# AD595_thermocouple_breakout_board-rev2.net
KiCad netlist of a schematic drawn in EAGLE
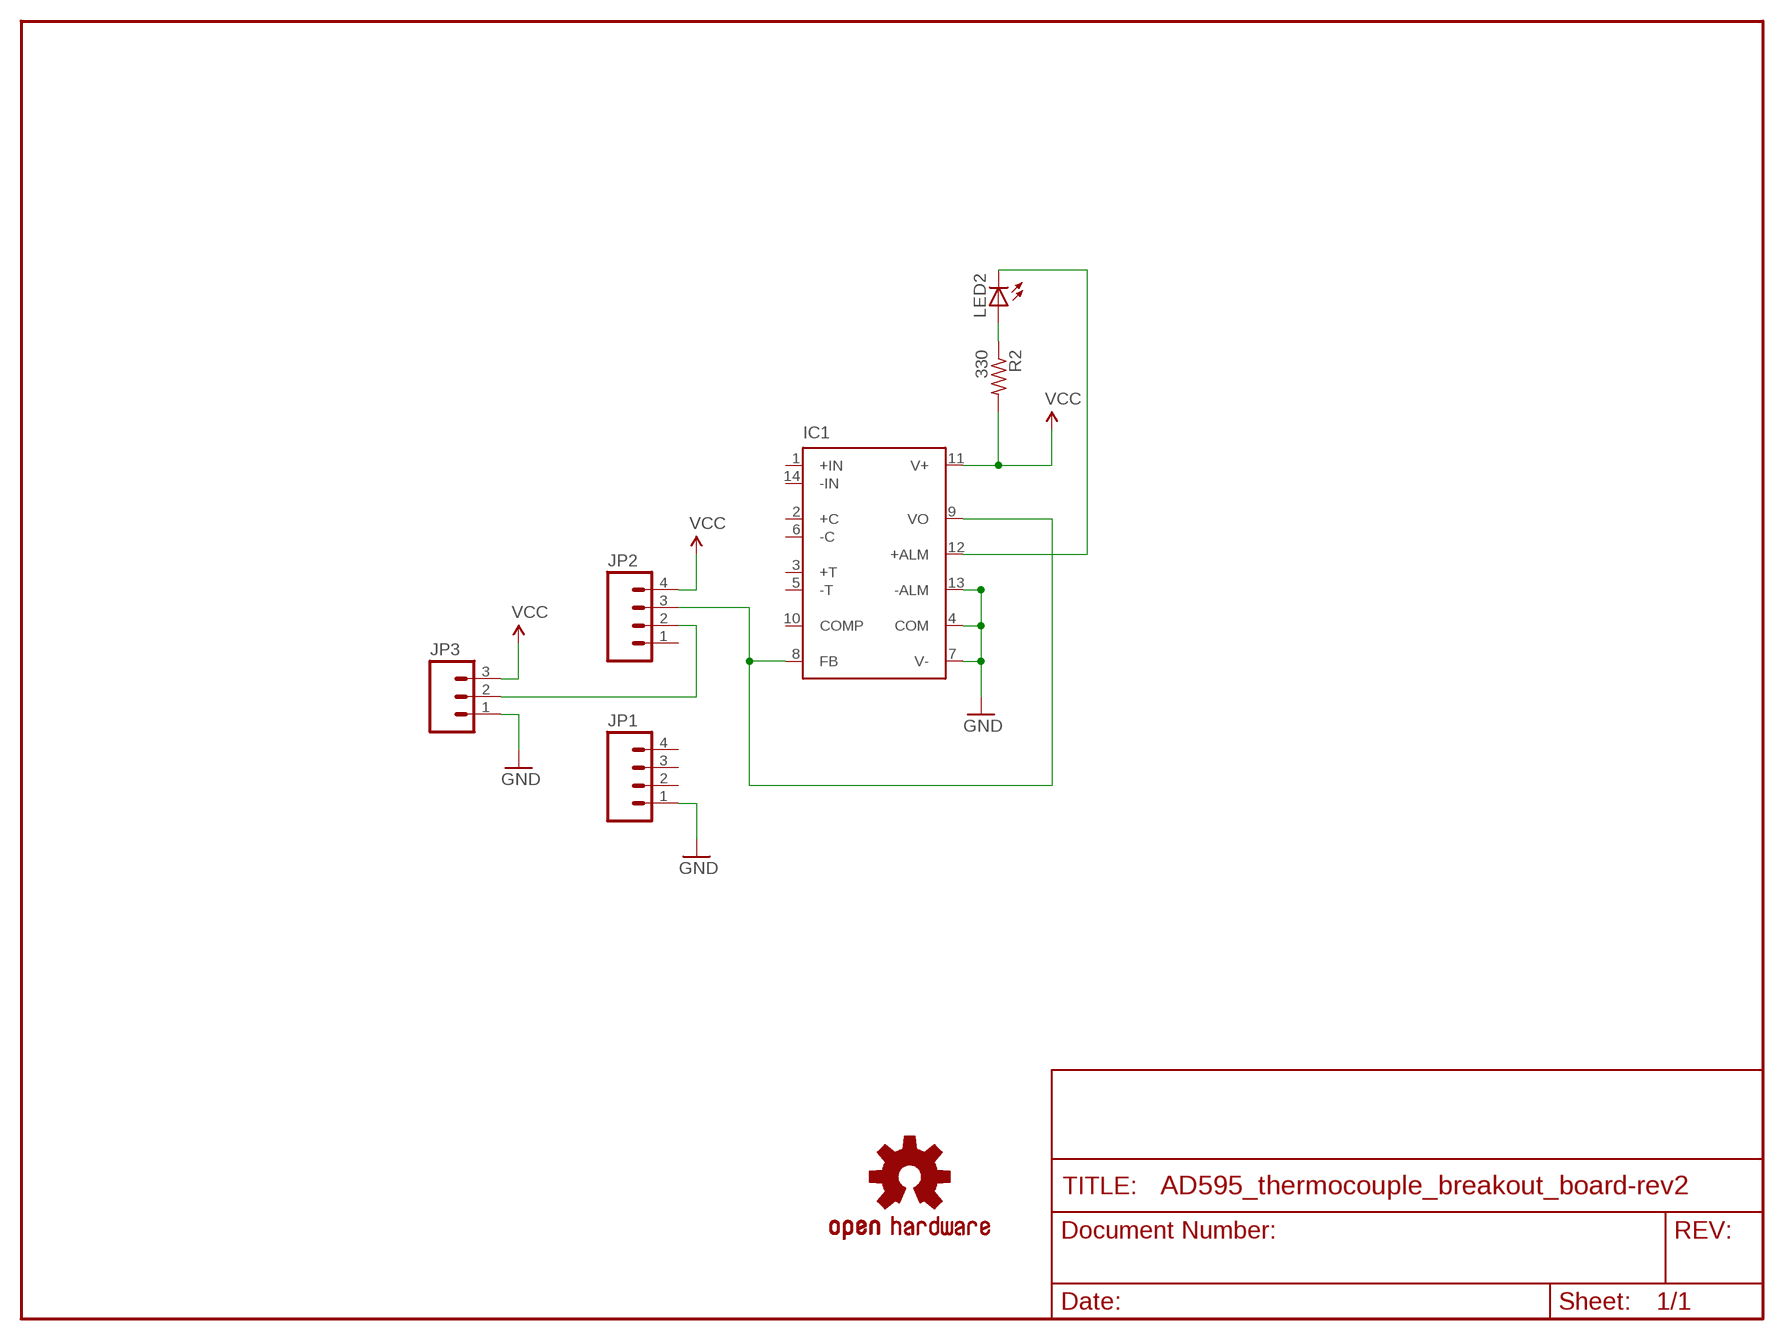
[diagram p0: schematic, sheet 1]

(export (version "E")
  (design (tool "Eeschema 10.0.6"))
  (components
    (comp (ref "IC1")
      (value "AD595")
      (footprint "eagle-import:DIL14")
      (libsource (lib "eagle-import") (part "AD595"))
    )
    (comp (ref "JP1")
      (value "M04LOCK")
      (footprint "eagle-import:1X04_LOCK")
      (libsource (lib "eagle-import") (part "M04LOCK"))
    )
    (comp (ref "JP2")
      (value "M04LOCK")
      (footprint "eagle-import:1X04_LOCK")
      (libsource (lib "eagle-import") (part "M04LOCK"))
    )
    (comp (ref "JP3")
      (value "M03SCREW_LOCK")
      (footprint "eagle-import:SCREWTERMINAL-3.5MM-3_LOCK.007S")
      (libsource (lib "eagle-import") (part "M03SCREW_LOCK"))
    )
    (comp (ref "LED2")
      (value "LED5MM")
      (footprint "eagle-import:LED5MM")
      (libsource (lib "eagle-import") (part "LED5MM"))
    )
    (comp (ref "R2")
      (value "330")
      (footprint "eagle-import:0207_7")
      (libsource (lib "eagle-import") (part "R-US_0207/7"))
    )
    (comp (ref "U$1")
      (value "OSHW-LOGOS")
      (footprint "eagle-import:OSHW-LOGO-S")
      (libsource (lib "eagle-import") (part "OSHW-LOGOS"))
    )
  )
  (nets
    (net (code "1") (name "GND") (class "Default")
      (node (ref "IC1") (pin "13") (pinfunction "-ALM_13") (pintype "passive"))
      (node (ref "IC1") (pin "4") (pinfunction "COM_4") (pintype "power_in"))
      (node (ref "IC1") (pin "7") (pinfunction "V-_7") (pintype "power_in"))
      (node (ref "JP1") (pin "1") (pinfunction "1_1") (pintype "passive"))
      (node (ref "JP3") (pin "1") (pinfunction "1_1") (pintype "passive"))
    )
    (net (code "2") (name "Net-(IC1-+ALM)") (class "Default")
      (node (ref "IC1") (pin "12") (pinfunction "+ALM_12") (pintype "passive"))
      (node (ref "LED2") (pin "K") (pinfunction "C_K") (pintype "passive"))
    )
    (net (code "3") (name "Net-(IC1-FB)") (class "Default")
      (node (ref "IC1") (pin "8") (pinfunction "FB_8") (pintype "passive"))
      (node (ref "IC1") (pin "9") (pinfunction "VO_9") (pintype "output"))
      (node (ref "JP2") (pin "3") (pinfunction "3_3") (pintype "passive"))
    )
    (net (code "4") (name "Net-(JP2-Pad2)") (class "Default")
      (node (ref "JP2") (pin "2") (pinfunction "2_2") (pintype "passive"))
      (node (ref "JP3") (pin "2") (pinfunction "2_2") (pintype "passive"))
    )
    (net (code "5") (name "Net-(LED2-PadA)") (class "Default")
      (node (ref "LED2") (pin "A") (pinfunction "A_A") (pintype "passive"))
      (node (ref "R2") (pin "1") (pinfunction "1_1") (pintype "passive"))
    )
    (net (code "6") (name "VCC") (class "Default")
      (node (ref "IC1") (pin "11") (pinfunction "V+_11") (pintype "power_in"))
      (node (ref "JP2") (pin "4") (pinfunction "4_4") (pintype "passive"))
      (node (ref "JP3") (pin "3") (pinfunction "3_3") (pintype "passive"))
      (node (ref "R2") (pin "2") (pinfunction "2_2") (pintype "passive"))
    )
    (net (code "7") (name "unconnected-(IC1-+C-Pad2)") (class "Default")
      (node (ref "IC1") (pin "2") (pinfunction "+C_2") (pintype "input"))
    )
    (net (code "8") (name "unconnected-(IC1-+IN-Pad1)") (class "Default")
      (node (ref "IC1") (pin "1") (pinfunction "+IN_1") (pintype "input"))
    )
    (net (code "9") (name "unconnected-(IC1-+T-Pad3)") (class "Default")
      (node (ref "IC1") (pin "3") (pinfunction "+T_3") (pintype "passive"))
    )
    (net (code "10") (name "unconnected-(IC1--C-Pad6)") (class "Default")
      (node (ref "IC1") (pin "6") (pinfunction "-C_6") (pintype "input"))
    )
    (net (code "11") (name "unconnected-(IC1--IN-Pad14)") (class "Default")
      (node (ref "IC1") (pin "14") (pinfunction "-IN_14") (pintype "input"))
    )
    (net (code "12") (name "unconnected-(IC1--T-Pad5)") (class "Default")
      (node (ref "IC1") (pin "5") (pinfunction "-T_5") (pintype "passive"))
    )
    (net (code "13") (name "unconnected-(IC1-COMP-Pad10)") (class "Default")
      (node (ref "IC1") (pin "10") (pinfunction "COMP_10") (pintype "passive"))
    )
    (net (code "14") (name "unconnected-(JP1-Pad2)") (class "Default")
      (node (ref "JP1") (pin "2") (pinfunction "2_2") (pintype "passive"))
    )
    (net (code "15") (name "unconnected-(JP1-Pad3)") (class "Default")
      (node (ref "JP1") (pin "3") (pinfunction "3_3") (pintype "passive"))
    )
    (net (code "16") (name "unconnected-(JP1-Pad4)") (class "Default")
      (node (ref "JP1") (pin "4") (pinfunction "4_4") (pintype "passive"))
    )
    (net (code "17") (name "unconnected-(JP2-Pad1)") (class "Default")
      (node (ref "JP2") (pin "1") (pinfunction "1_1") (pintype "passive"))
    )
  )
)
